# 2019_VL53_Fixator.net
KiCad netlist of a schematic drawn in Altium Designer
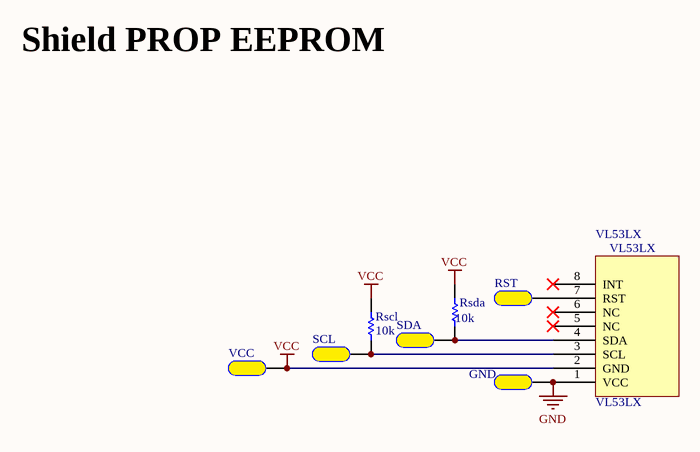
[diagram p0: 2019_VL53_Fixator.SchDoc]

(export (version "E")
  (design (tool "Eeschema 10.0.6"))
  (components
    (comp (ref "GND")
      (value "Pad_CMS")
      (footprint "PAD_CMS_10x3")
      (description "Pad pour souder un fil")
      (fields (field (name "PUBLISHER") "Damien Guitton"))
      (libsource (lib "Connecteur") (part "Pad_CMS"))
    )
    (comp (ref "Rscl")
      (value "10k")
      (footprint "R0805_N")
      (description "Resistor")
      (fields (field (name "PUBLISHER") "Altium Limited"))
      (libsource (lib "_ROBOT") (part "Resistor"))
    )
    (comp (ref "Rsda")
      (value "10k")
      (footprint "R0805_N")
      (description "Resistor")
      (fields (field (name "PUBLISHER") "Altium Limited"))
      (libsource (lib "_ROBOT") (part "Resistor"))
    )
    (comp (ref "RST")
      (value "Pad_CMS")
      (footprint "PAD_CMS_10x3")
      (description "Pad pour souder un fil")
      (fields (field (name "PUBLISHER") "Damien Guitton"))
      (libsource (lib "Connecteur") (part "Pad_CMS"))
    )
    (comp (ref "SCL")
      (value "Pad_CMS")
      (footprint "PAD_CMS_10x3")
      (description "Pad pour souder un fil")
      (fields (field (name "PUBLISHER") "Damien Guitton"))
      (libsource (lib "Connecteur") (part "Pad_CMS"))
    )
    (comp (ref "SDA")
      (value "Pad_CMS")
      (footprint "PAD_CMS_10x3")
      (description "Pad pour souder un fil")
      (fields (field (name "PUBLISHER") "Damien Guitton"))
      (libsource (lib "Connecteur") (part "Pad_CMS"))
    )
    (comp (ref "VCC")
      (value "Pad_CMS")
      (footprint "PAD_CMS_10x3")
      (description "Pad pour souder un fil")
      (fields (field (name "PUBLISHER") "Damien Guitton"))
      (libsource (lib "Connecteur") (part "Pad_CMS"))
    )
    (comp (ref "VL53LX") (value "VL53LX") (footprint "VL53LX") (libsource (lib "_ROBOT") (part "VL53LX")))
  )
  (nets
    (net (code "1") (name "GND") (class "Default")
      (node (ref "GND") (pin "1") (pinfunction "1_1") (pintype "passive"))
      (node (ref "VL53LX") (pin "1") (pinfunction "VCC_1") (pintype "passive"))
    )
    (net (code "2") (name "Net-(VL53LX-RST)") (class "Default")
      (node (ref "RST") (pin "1") (pinfunction "1_1") (pintype "passive"))
      (node (ref "VL53LX") (pin "7") (pinfunction "RST_7") (pintype "passive"))
    )
    (net (code "3") (name "Net-(VL53LX-SCL)") (class "Default")
      (node (ref "Rscl") (pin "2") (pinfunction "2_2") (pintype "passive"))
      (node (ref "SCL") (pin "1") (pinfunction "1_1") (pintype "passive"))
      (node (ref "VL53LX") (pin "3") (pinfunction "SCL_3") (pintype "passive"))
    )
    (net (code "4") (name "Net-(VL53LX-SDA)") (class "Default")
      (node (ref "Rsda") (pin "2") (pinfunction "2_2") (pintype "passive"))
      (node (ref "SDA") (pin "1") (pinfunction "1_1") (pintype "passive"))
      (node (ref "VL53LX") (pin "4") (pinfunction "SDA_4") (pintype "passive"))
    )
    (net (code "5") (name "VCC") (class "Default")
      (node (ref "Rscl") (pin "1") (pinfunction "1_1") (pintype "passive"))
      (node (ref "Rsda") (pin "1") (pinfunction "1_1") (pintype "passive"))
      (node (ref "VCC") (pin "1") (pinfunction "1_1") (pintype "passive"))
      (node (ref "VL53LX") (pin "2") (pinfunction "GND_2") (pintype "passive"))
    )
    (net (code "6") (name "unconnected-(VL53LX-INT-Pad8)") (class "Default")
      (node (ref "VL53LX") (pin "8") (pinfunction "INT_8") (pintype "passive+no_connect"))
    )
    (net (code "7") (name "unconnected-(VL53LX-NC-Pad5)") (class "Default")
      (node (ref "VL53LX") (pin "5") (pinfunction "NC_5") (pintype "passive+no_connect"))
    )
    (net (code "8") (name "unconnected-(VL53LX-NC-Pad6)") (class "Default")
      (node (ref "VL53LX") (pin "6") (pinfunction "NC_6") (pintype "passive+no_connect"))
    )
  )
)
